# Flybuck.net
KiCad netlist of a schematic drawn in Altium Designer
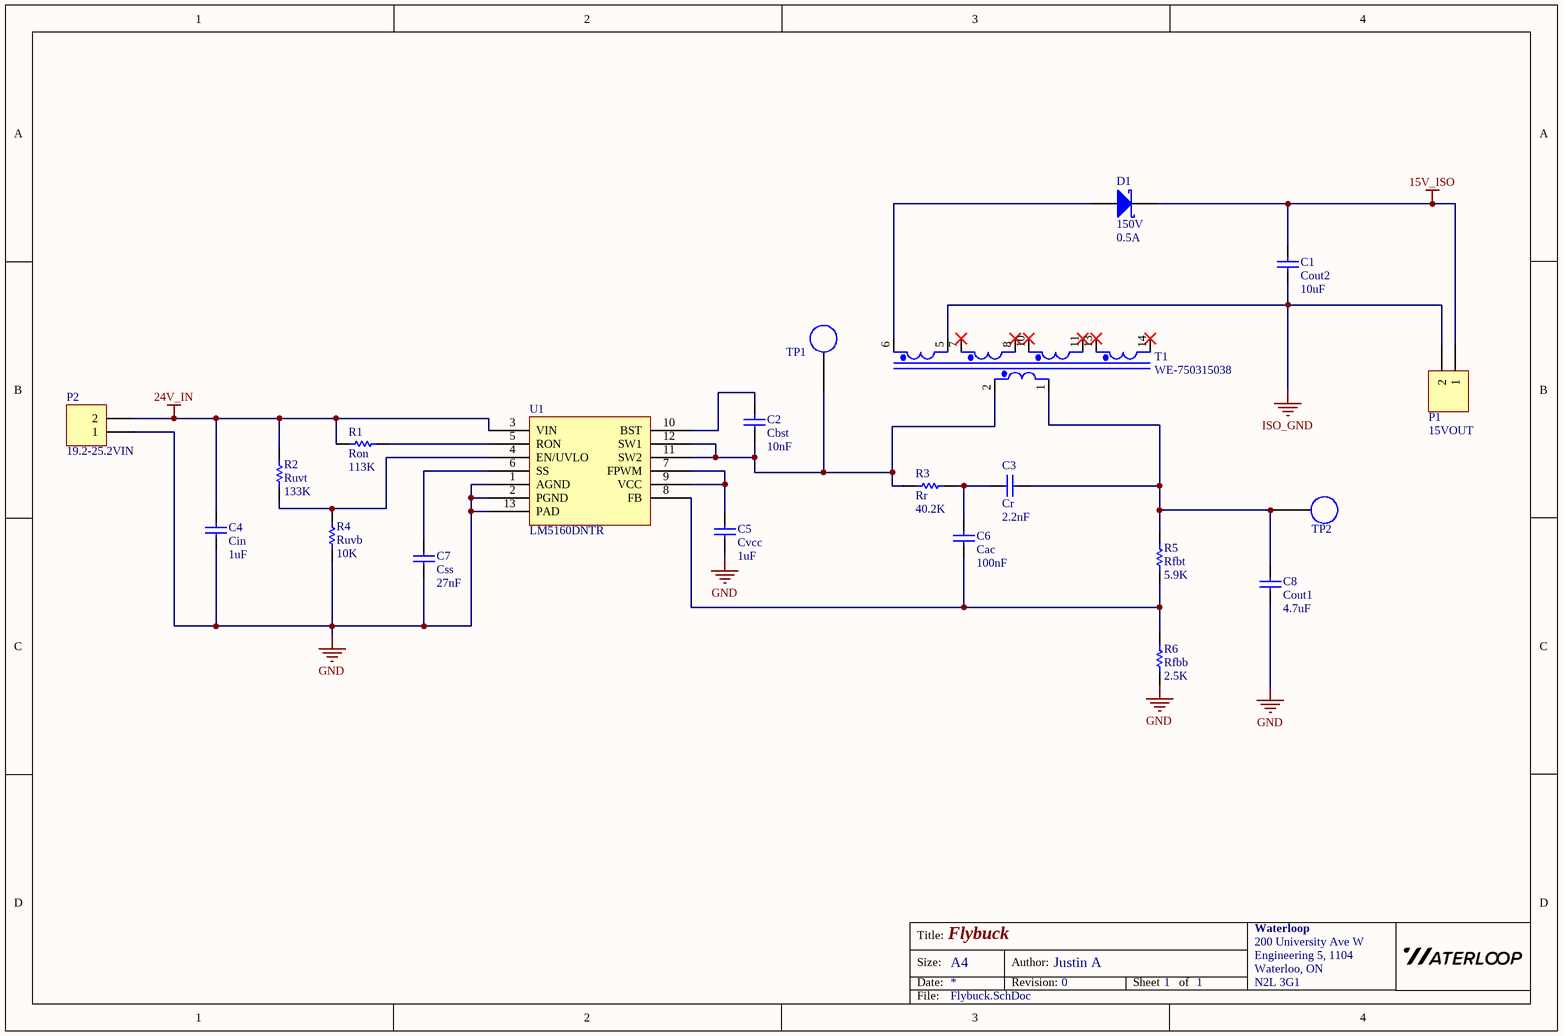
[diagram p0: Flybuck.SchDoc]

(export (version "E")
  (design (tool "Eeschema 10.0.6"))
  (components
    (comp (ref "C1")
      (value "Cout2")
      (footprint "0805 - Capacitor")
      (description "Nonpolarized Capacitor")
      (fields (field (name "ALTIUM_VALUE") "10uF"))
      (libsource (lib "General") (part "Capacitor - Nonpolarized"))
    )
    (comp (ref "C2")
      (value "Cbst")
      (footprint "0805 - Capacitor")
      (description "Nonpolarized Capacitor")
      (fields (field (name "ALTIUM_VALUE") "10nF"))
      (libsource (lib "General") (part "Capacitor - Nonpolarized"))
    )
    (comp (ref "C3")
      (value "Cr")
      (footprint "0805 - Capacitor")
      (description "Nonpolarized Capacitor")
      (fields (field (name "ALTIUM_VALUE") "2.2nF"))
      (libsource (lib "General") (part "Capacitor - Nonpolarized"))
    )
    (comp (ref "C4")
      (value "Cin")
      (footprint "0805 - Capacitor")
      (description "Nonpolarized Capacitor")
      (fields (field (name "ALTIUM_VALUE") "1uF"))
      (libsource (lib "General") (part "Capacitor - Nonpolarized"))
    )
    (comp (ref "C5")
      (value "Cvcc")
      (footprint "0805 - Capacitor")
      (description "Nonpolarized Capacitor")
      (fields (field (name "ALTIUM_VALUE") "1uF"))
      (libsource (lib "General") (part "Capacitor - Nonpolarized"))
    )
    (comp (ref "C6")
      (value "Cac")
      (footprint "0805 - Capacitor")
      (description "Nonpolarized Capacitor")
      (fields (field (name "ALTIUM_VALUE") "100nF"))
      (libsource (lib "General") (part "Capacitor - Nonpolarized"))
    )
    (comp (ref "C7")
      (value "Css")
      (footprint "0805 - Capacitor")
      (description "Nonpolarized Capacitor")
      (fields (field (name "ALTIUM_VALUE") "27nF"))
      (libsource (lib "General") (part "Capacitor - Nonpolarized"))
    )
    (comp (ref "C8")
      (value "Cout1")
      (footprint "0805 - Capacitor")
      (description "Nonpolarized Capacitor")
      (fields (field (name "ALTIUM_VALUE") "4.7uF"))
      (libsource (lib "General") (part "Capacitor - Nonpolarized"))
    )
    (comp (ref "D1")
      (value "0.5A")
      (footprint "SOD123 - DIODE")
      (description "Schottky Rectifier")
      (fields (field (name "RATING") "150V") (field (name "Comment") "Diode - Schottky"))
      (libsource (lib "General") (part "Diode - Schottky"))
    )
    (comp (ref "P1")
      (value "15VOUT")
      (footprint "HDR1X2")
      (description "1x2 Pin Header")
      (libsource (lib "GeneralConnectors") (part "1x2 Header"))
    )
    (comp (ref "P2")
      (value "19.2-25.2VIN")
      (footprint "HDR1X2")
      (description "1x2 Pin Header")
      (libsource (lib "") (part "1x2 Header_1"))
    )
    (comp (ref "R1")
      (value "Ron")
      (footprint "0603 - Resistor")
      (description "Resistor")
      (fields (field (name "ALTIUM_VALUE") "113K"))
      (libsource (lib "General") (part "Resistor"))
    )
    (comp (ref "R2")
      (value "Ruvt")
      (footprint "0603 - Resistor")
      (description "Resistor")
      (fields (field (name "ALTIUM_VALUE") "133K"))
      (libsource (lib "General") (part "Resistor"))
    )
    (comp (ref "R3")
      (value "Rr")
      (footprint "0603 - Resistor")
      (description "Resistor")
      (fields (field (name "ALTIUM_VALUE") "40.2K"))
      (libsource (lib "General") (part "Resistor"))
    )
    (comp (ref "R4")
      (value "Ruvb")
      (footprint "0603 - Resistor")
      (description "Resistor")
      (fields (field (name "ALTIUM_VALUE") "10K"))
      (libsource (lib "General") (part "Resistor"))
    )
    (comp (ref "R5")
      (value "Rfbt")
      (footprint "0603 - Resistor")
      (description "Resistor")
      (fields (field (name "ALTIUM_VALUE") "5.9K"))
      (libsource (lib "General") (part "Resistor"))
    )
    (comp (ref "R6")
      (value "Rfbb")
      (footprint "0603 - Resistor")
      (description "Resistor")
      (fields (field (name "ALTIUM_VALUE") "2.5K"))
      (libsource (lib "General") (part "Resistor"))
    )
    (comp (ref "T1")
      (value "WE-750315038")
      (footprint "WE-750315038")
      (description "TRANSFORMER 36.5uH 300mA THT 26VDC")
      (fields
        (field (name "MANUFACTURER") "Würth Elektronik")
        (field (name "MANUFACTURER PART NUMBER") "750315038")
      )
      (libsource (lib "MC") (part "WE-750315038"))
    )
    (comp (ref "TP1")
      (value "Test Point")
      (footprint "Test Point")
      (description "Test Point!")
      (libsource (lib "General") (part "Test Point"))
    )
    (comp (ref "TP2")
      (value "Test Point")
      (footprint "Test Point")
      (description "Test Point!")
      (libsource (lib "General") (part "Test Point"))
    )
    (comp (ref "U1")
      (value "LM5160DNTR")
      (footprint "LM5160DNTR")
      (description "IC REG BUCK FLYBCK ADJ 12WSON")
      (fields (field (name "MANUFACTURER") "Texas Instruments"))
      (libsource (lib "MC") (part "LM5160DNTR"))
    )
  )
  (nets
    (net (code "1") (name "15V_ISO") (class "Default")
      (node (ref "C1") (pin "2") (pinfunction "2_2") (pintype "passive"))
      (node (ref "D1") (pin "2") (pinfunction "K_2") (pintype "passive"))
      (node (ref "P1") (pin "1") (pinfunction "1_1") (pintype "passive"))
    )
    (net (code "2") (name "24V_IN") (class "Default")
      (node (ref "C4") (pin "2") (pinfunction "2_2") (pintype "passive"))
      (node (ref "P2") (pin "2") (pinfunction "2_2") (pintype "passive"))
      (node (ref "R1") (pin "1") (pinfunction "1_1") (pintype "passive"))
      (node (ref "R2") (pin "2") (pinfunction "2_2") (pintype "passive"))
      (node (ref "U1") (pin "3") (pinfunction "VIN_3") (pintype "power_in"))
    )
    (net (code "3") (name "GND") (class "Default")
      (node (ref "C4") (pin "1") (pinfunction "1_1") (pintype "passive"))
      (node (ref "C5") (pin "1") (pinfunction "1_1") (pintype "passive"))
      (node (ref "C7") (pin "1") (pinfunction "1_1") (pintype "passive"))
      (node (ref "C8") (pin "1") (pinfunction "1_1") (pintype "passive"))
      (node (ref "P2") (pin "1") (pinfunction "1_1") (pintype "passive"))
      (node (ref "R4") (pin "1") (pinfunction "1_1") (pintype "passive"))
      (node (ref "R6") (pin "1") (pinfunction "1_1") (pintype "passive"))
      (node (ref "U1") (pin "1") (pinfunction "AGND_1") (pintype "passive"))
      (node (ref "U1") (pin "13") (pinfunction "PAD_13") (pintype "passive"))
      (node (ref "U1") (pin "2") (pinfunction "PGND_2") (pintype "passive"))
    )
    (net (code "4") (name "ISO_GND") (class "Default")
      (node (ref "C1") (pin "1") (pinfunction "1_1") (pintype "passive"))
      (node (ref "P1") (pin "2") (pinfunction "2_2") (pintype "passive"))
      (node (ref "T1") (pin "5") (pinfunction "Sec-_5") (pintype "passive"))
    )
    (net (code "5") (name "Net-(C3-Pad2)") (class "Default")
      (node (ref "C3") (pin "2") (pinfunction "2_2") (pintype "passive"))
      (node (ref "C6") (pin "2") (pinfunction "2_2") (pintype "passive"))
      (node (ref "R3") (pin "2") (pinfunction "2_2") (pintype "passive"))
    )
    (net (code "6") (name "Net-(D1-A)") (class "Default")
      (node (ref "D1") (pin "1") (pinfunction "A_1") (pintype "passive"))
      (node (ref "T1") (pin "6") (pinfunction "Sec+_6") (pintype "passive"))
    )
    (net (code "7") (name "Net-(T1-Pri+)") (class "Default")
      (node (ref "C2") (pin "1") (pinfunction "1_1") (pintype "passive"))
      (node (ref "R3") (pin "1") (pinfunction "1_1") (pintype "passive"))
      (node (ref "T1") (pin "2") (pinfunction "Pri+_2") (pintype "passive"))
      (node (ref "TP1") (pin "0") (pinfunction "0_0") (pintype "passive"))
      (node (ref "U1") (pin "11") (pinfunction "SW2_11") (pintype "passive"))
      (node (ref "U1") (pin "12") (pinfunction "SW1_12") (pintype "passive"))
    )
    (net (code "8") (name "Net-(T1-Pri-)") (class "Default")
      (node (ref "C3") (pin "1") (pinfunction "1_1") (pintype "passive"))
      (node (ref "C8") (pin "2") (pinfunction "2_2") (pintype "passive"))
      (node (ref "R5") (pin "2") (pinfunction "2_2") (pintype "passive"))
      (node (ref "T1") (pin "1") (pinfunction "Pri-_1") (pintype "passive"))
      (node (ref "TP2") (pin "0") (pinfunction "0_0") (pintype "passive"))
    )
    (net (code "9") (name "Net-(U1-BST)") (class "Default")
      (node (ref "C2") (pin "2") (pinfunction "2_2") (pintype "passive"))
      (node (ref "U1") (pin "10") (pinfunction "BST_10") (pintype "passive"))
    )
    (net (code "10") (name "Net-(U1-EN{slash}UVLO)") (class "Default")
      (node (ref "R2") (pin "1") (pinfunction "1_1") (pintype "passive"))
      (node (ref "R4") (pin "2") (pinfunction "2_2") (pintype "passive"))
      (node (ref "U1") (pin "4") (pinfunction "EN/UVLO_4") (pintype "passive"))
    )
    (net (code "11") (name "Net-(U1-FB)") (class "Default")
      (node (ref "C6") (pin "1") (pinfunction "1_1") (pintype "passive"))
      (node (ref "R5") (pin "1") (pinfunction "1_1") (pintype "passive"))
      (node (ref "R6") (pin "2") (pinfunction "2_2") (pintype "passive"))
      (node (ref "U1") (pin "8") (pinfunction "FB_8") (pintype "passive"))
    )
    (net (code "12") (name "Net-(U1-FPWM)") (class "Default")
      (node (ref "C5") (pin "2") (pinfunction "2_2") (pintype "passive"))
      (node (ref "U1") (pin "7") (pinfunction "FPWM_7") (pintype "passive"))
      (node (ref "U1") (pin "9") (pinfunction "VCC_9") (pintype "passive"))
    )
    (net (code "13") (name "Net-(U1-RON)") (class "Default")
      (node (ref "R1") (pin "2") (pinfunction "2_2") (pintype "passive"))
      (node (ref "U1") (pin "5") (pinfunction "RON_5") (pintype "passive"))
    )
    (net (code "14") (name "Net-(U1-SS)") (class "Default")
      (node (ref "C7") (pin "2") (pinfunction "2_2") (pintype "passive"))
      (node (ref "U1") (pin "6") (pinfunction "SS_6") (pintype "passive"))
    )
    (net (code "15") (name "unconnected-(T1-Sec+-Pad7)") (class "Default")
      (node (ref "T1") (pin "7") (pinfunction "Sec+_7") (pintype "passive+no_connect"))
    )
    (net (code "16") (name "unconnected-(T1-Sec+-Pad10)") (class "Default")
      (node (ref "T1") (pin "10") (pinfunction "Sec+_10") (pintype "passive+no_connect"))
    )
    (net (code "17") (name "unconnected-(T1-Sec+-Pad13)") (class "Default")
      (node (ref "T1") (pin "13") (pinfunction "Sec+_13") (pintype "passive+no_connect"))
    )
    (net (code "18") (name "unconnected-(T1-Sec--Pad8)") (class "Default")
      (node (ref "T1") (pin "8") (pinfunction "Sec-_8") (pintype "passive+no_connect"))
    )
    (net (code "19") (name "unconnected-(T1-Sec--Pad11)") (class "Default")
      (node (ref "T1") (pin "11") (pinfunction "Sec-_11") (pintype "passive+no_connect"))
    )
    (net (code "20") (name "unconnected-(T1-Sec--Pad14)") (class "Default")
      (node (ref "T1") (pin "14") (pinfunction "Sec-_14") (pintype "passive+no_connect"))
    )
  )
)
